# Peripherals.net
KiCad netlist of a schematic drawn in Altium Designer
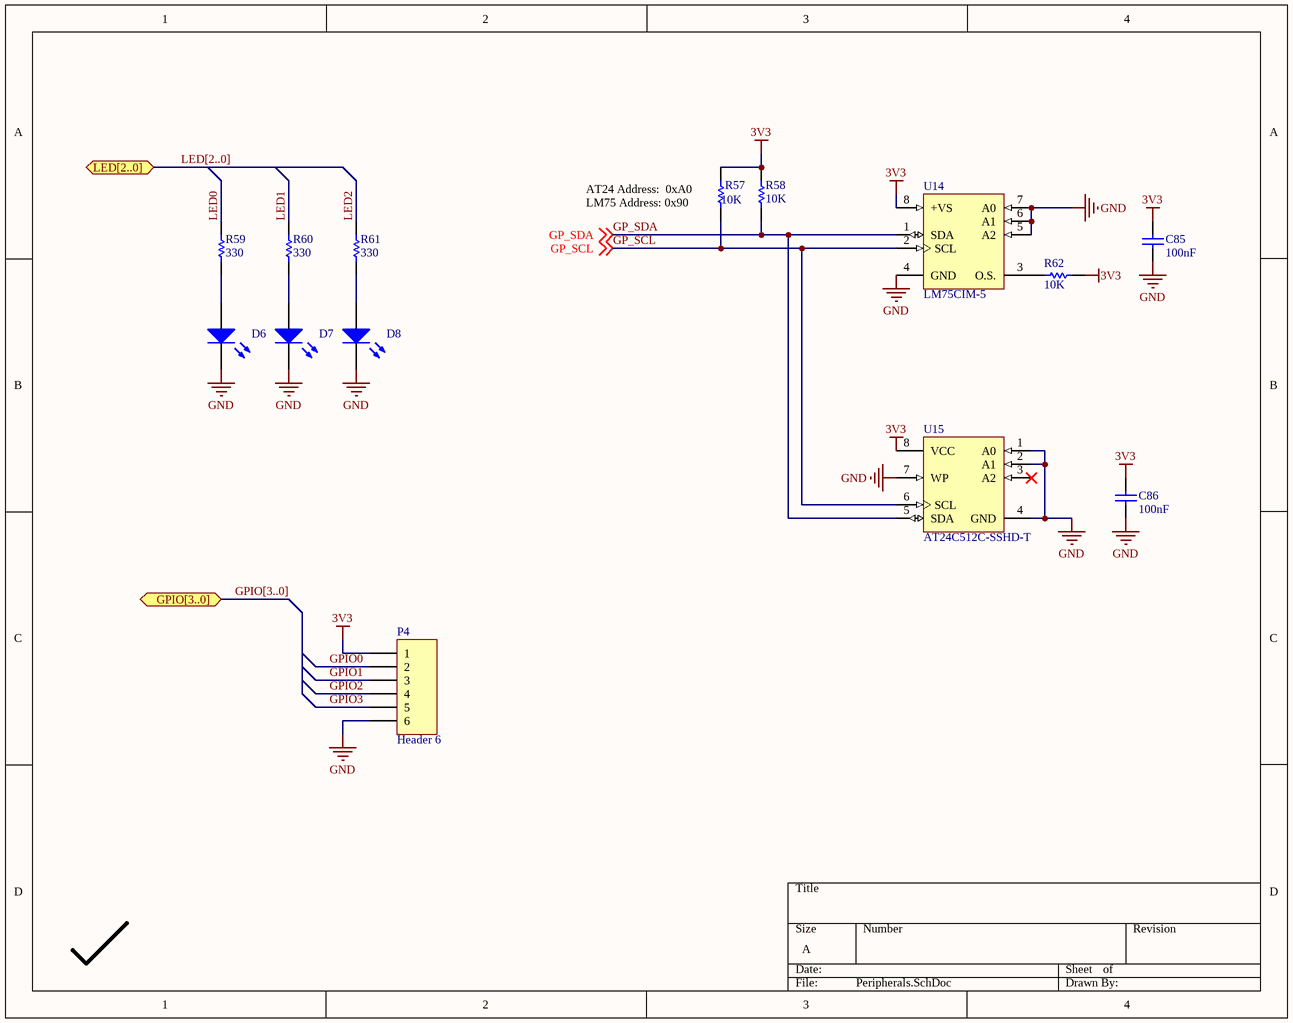
[diagram p0: Peripherals.SchDoc]

(export (version "E")
  (design (tool "Eeschema 10.0.6"))
  (components
    (comp (ref "C85")
      (value "100nF")
      (footprint "0603PKG")
      (description "Capacitor")
      (fields (field (name "Comment") "Cap") (field (name "PUBLISHER") "Altium Limited"))
      (libsource (lib "Miscellaneous Devices") (part "Cap"))
    )
    (comp (ref "C86")
      (value "100nF")
      (footprint "0603PKG")
      (description "Capacitor")
      (fields (field (name "Comment") "Cap") (field (name "PUBLISHER") "Altium Limited"))
      (libsource (lib "Miscellaneous Devices") (part "Cap"))
    )
    (comp (ref "D6")
      (value "LED0")
      (footprint "C0805")
      (description "Typical INFRARED GaAs LED")
      (fields (field (name "PUBLISHER") "Altium Limited"))
      (libsource (lib "Miscellaneous Devices") (part "LED0"))
    )
    (comp (ref "D7")
      (value "LED0")
      (footprint "C0805")
      (description "Typical INFRARED GaAs LED")
      (fields (field (name "PUBLISHER") "Altium Limited"))
      (libsource (lib "Miscellaneous Devices") (part "LED0"))
    )
    (comp (ref "D8")
      (value "LED0")
      (footprint "C0805")
      (description "Typical INFRARED GaAs LED")
      (fields (field (name "PUBLISHER") "Altium Limited"))
      (libsource (lib "Miscellaneous Devices") (part "LED0"))
    )
    (comp (ref "P4")
      (value "Header 6")
      (footprint "HDR1X6")
      (description "Header, 6-Pin")
      (fields (field (name "PUBLISHER") "Altium Limited"))
      (libsource (lib "Miscellaneous Connectors") (part "Header 6"))
    )
    (comp (ref "R57")
      (value "10K")
      (footprint "0603PKG")
      (description "Semiconductor Resistor")
      (fields (field (name "Comment") "Res Semi") (field (name "PUBLISHER") "Altium Limited"))
      (libsource (lib "Miscellaneous Devices") (part "Res Semi"))
    )
    (comp (ref "R58")
      (value "10K")
      (footprint "0603PKG")
      (description "Semiconductor Resistor")
      (fields (field (name "Comment") "Res Semi") (field (name "PUBLISHER") "Altium Limited"))
      (libsource (lib "Miscellaneous Devices") (part "Res Semi"))
    )
    (comp (ref "R59")
      (value "330")
      (footprint "0603PKG")
      (description "Semiconductor Resistor")
      (fields (field (name "Comment") "Res Semi") (field (name "PUBLISHER") "Altium Limited"))
      (libsource (lib "Miscellaneous Devices") (part "Res Semi"))
    )
    (comp (ref "R60")
      (value "330")
      (footprint "0603PKG")
      (description "Semiconductor Resistor")
      (fields (field (name "Comment") "Res Semi") (field (name "PUBLISHER") "Altium Limited"))
      (libsource (lib "Miscellaneous Devices") (part "Res Semi"))
    )
    (comp (ref "R61")
      (value "330")
      (footprint "0603PKG")
      (description "Semiconductor Resistor")
      (fields (field (name "Comment") "Res Semi") (field (name "PUBLISHER") "Altium Limited"))
      (libsource (lib "Miscellaneous Devices") (part "Res Semi"))
    )
    (comp (ref "R62")
      (value "10K")
      (footprint "0603PKG")
      (description "Semiconductor Resistor")
      (fields (field (name "Comment") "Res Semi") (field (name "PUBLISHER") "Altium Limited"))
      (libsource (lib "Miscellaneous Devices") (part "Res Semi"))
    )
    (comp (ref "U14")
      (value "LM75CIM-5")
      (footprint "8S1_N")
      (description "Digital Temperature Sensor and Thermal Watchdog with Two-Wire Interface, 8 pin MINI SOIC")
      (fields
        (field (name "PARTNUMBER") "LM75CIMMX-5/NOPB")
        (field (name "MANUFACTURER") "National Semiconductor")
      )
      (libsource (lib "National Semiconductor Temperature Sensor") (part "LM75CIMMX-5/NOPB"))
    )
    (comp (ref "U15")
      (value "AT24C512C-SSHD-T")
      (footprint "8S1_N")
      (description "1Kbit (128 x 8), 2-wire Bus Automotive Serial EEPROM with Write Protect, 2.5V, 8-Pin SOIC, Bulk")
      (libsource (lib "Atmel Serial EEPROM") (part "AT24C01BN-SP25-B"))
    )
  )
  (nets
    (net (code "1") (name "/GPIO0") (class "Default")
      (node (ref "P4") (pin "2") (pinfunction "2_2") (pintype "passive"))
    )
    (net (code "2") (name "/GPIO1") (class "Default")
      (node (ref "P4") (pin "3") (pinfunction "3_3") (pintype "passive"))
    )
    (net (code "3") (name "/GPIO2") (class "Default")
      (node (ref "P4") (pin "4") (pinfunction "4_4") (pintype "passive"))
    )
    (net (code "4") (name "/GPIO3") (class "Default")
      (node (ref "P4") (pin "5") (pinfunction "5_5") (pintype "passive"))
    )
    (net (code "6") (name "/LED0") (class "Default")
      (node (ref "R59") (pin "2") (pinfunction "2_2") (pintype "passive"))
    )
    (net (code "7") (name "/LED1") (class "Default")
      (node (ref "R60") (pin "2") (pinfunction "2_2") (pintype "passive"))
    )
    (net (code "8") (name "/LED2") (class "Default")
      (node (ref "R61") (pin "2") (pinfunction "2_2") (pintype "passive"))
    )
    (net (code "10") (name "3V3") (class "Default")
      (node (ref "C85") (pin "2") (pinfunction "2_2") (pintype "passive"))
      (node (ref "C86") (pin "2") (pinfunction "2_2") (pintype "passive"))
      (node (ref "P4") (pin "1") (pinfunction "1_1") (pintype "passive"))
      (node (ref "R57") (pin "1") (pinfunction "1_1") (pintype "passive"))
      (node (ref "R58") (pin "1") (pinfunction "1_1") (pintype "passive"))
      (node (ref "R62") (pin "1") (pinfunction "1_1") (pintype "passive"))
      (node (ref "U14") (pin "8") (pinfunction "+VS_8") (pintype "input"))
      (node (ref "U15") (pin "8") (pinfunction "VCC_8") (pintype "power_in"))
    )
    (net (code "11") (name "GND") (class "Default")
      (node (ref "C85") (pin "1") (pinfunction "1_1") (pintype "passive"))
      (node (ref "C86") (pin "1") (pinfunction "1_1") (pintype "passive"))
      (node (ref "D6") (pin "2") (pinfunction "K_2") (pintype "passive"))
      (node (ref "D7") (pin "2") (pinfunction "K_2") (pintype "passive"))
      (node (ref "D8") (pin "2") (pinfunction "K_2") (pintype "passive"))
      (node (ref "P4") (pin "6") (pinfunction "6_6") (pintype "passive"))
      (node (ref "U14") (pin "4") (pinfunction "GND_4") (pintype "power_in"))
      (node (ref "U14") (pin "5") (pinfunction "A2_5") (pintype "input"))
      (node (ref "U14") (pin "6") (pinfunction "A1_6") (pintype "input"))
      (node (ref "U14") (pin "7") (pinfunction "A0_7") (pintype "input"))
      (node (ref "U15") (pin "1") (pinfunction "A0_1") (pintype "input"))
      (node (ref "U15") (pin "2") (pinfunction "A1_2") (pintype "input"))
      (node (ref "U15") (pin "4") (pinfunction "GND_4") (pintype "power_in"))
      (node (ref "U15") (pin "7") (pinfunction "WP_7") (pintype "input"))
    )
    (net (code "12") (name "GP_SCL") (class "Default")
      (node (ref "R57") (pin "2") (pinfunction "2_2") (pintype "passive"))
      (node (ref "U14") (pin "2") (pinfunction "SCL_2") (pintype "input"))
      (node (ref "U15") (pin "6") (pinfunction "SCL_6") (pintype "input"))
    )
    (net (code "13") (name "GP_SDA") (class "Default")
      (node (ref "R58") (pin "2") (pinfunction "2_2") (pintype "passive"))
      (node (ref "U14") (pin "1") (pinfunction "SDA_1") (pintype "bidirectional"))
      (node (ref "U15") (pin "5") (pinfunction "SDA_5") (pintype "bidirectional"))
    )
    (net (code "14") (name "Net-(D6-A)") (class "Default")
      (node (ref "D6") (pin "1") (pinfunction "A_1") (pintype "passive"))
      (node (ref "R59") (pin "1") (pinfunction "1_1") (pintype "passive"))
    )
    (net (code "15") (name "Net-(D7-A)") (class "Default")
      (node (ref "D7") (pin "1") (pinfunction "A_1") (pintype "passive"))
      (node (ref "R60") (pin "1") (pinfunction "1_1") (pintype "passive"))
    )
    (net (code "16") (name "Net-(D8-A)") (class "Default")
      (node (ref "D8") (pin "1") (pinfunction "A_1") (pintype "passive"))
      (node (ref "R61") (pin "1") (pinfunction "1_1") (pintype "passive"))
    )
    (net (code "17") (name "Net-(U14-O.S.)") (class "Default")
      (node (ref "R62") (pin "2") (pinfunction "2_2") (pintype "passive"))
      (node (ref "U14") (pin "3") (pinfunction "O.S._3") (pintype "open_collector"))
    )
    (net (code "18") (name "unconnected-(U15-A2-Pad3)") (class "Default")
      (node (ref "U15") (pin "3") (pinfunction "A2_3") (pintype "input+no_connect"))
    )
  )
)
